# SCH1_MCU.net
KiCad netlist of a schematic drawn in Altium Designer
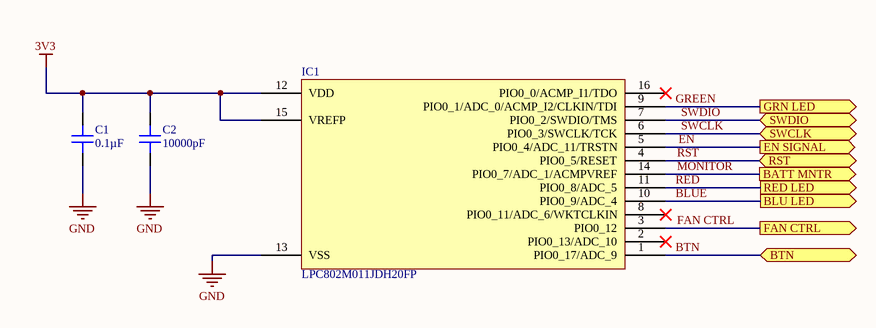
[diagram p0: SCH1_MCU.SchDoc]

(export (version "E")
  (design (tool "Eeschema 10.0.6"))
  (components
    (comp (ref "C1")
      (value "0.1µF")
      (footprint "CAP 0402_1005")
      (description "CAP CER 0.1UF 25V X5R 0402")
      (fields (field (name "PART NUMBER") "CC0402KRX5R8BB104") (field (name "MANUFACTURER") "Yageo"))
      (libsource (lib "Celestial Altium Library - altium_library") (part "Capacitor"))
    )
    (comp (ref "C2")
      (value "10000pF")
      (footprint "CAP 0402_1005")
      (description "CAP CER 10000PF 25V X5R 0402")
      (fields
        (field (name "PART NUMBER") "CGA2B2X5R1E103M050BA")
        (field (name "MANUFACTURER") "TDK Corporation")
      )
      (libsource (lib "Celestial Altium Library - altium_library") (part "Capacitor"))
    )
    (comp (ref "IC1")
      (value "LPC802M011JDH20FP")
      (footprint "NXP TSSOP-16")
      (description "Integrated CIrcuit")
      (libsource (lib "SCH - ARM CORTEX - NXP LPC80X 16PIN") (part "NXP LPC802 16PIN"))
    )
  )
  (nets
    (net (code "1") (name "/BLUE") (class "Default")
      (node (ref "IC1") (pin "10") (pinfunction "PIO0_9/ADC_4_10") (pintype "passive"))
    )
    (net (code "2") (name "/BTN") (class "Default")
      (node (ref "IC1") (pin "1") (pinfunction "PIO0_17/ADC_9_1") (pintype "passive"))
    )
    (net (code "3") (name "/EN") (class "Default")
      (node (ref "IC1") (pin "5") (pinfunction "PIO0_4/ADC_11/TRSTN_5") (pintype "passive"))
    )
    (net (code "4") (name "/FAN CTRL") (class "Default")
      (node (ref "IC1") (pin "3") (pinfunction "PIO0_12_3") (pintype "passive"))
    )
    (net (code "5") (name "/GREEN") (class "Default")
      (node (ref "IC1") (pin "9") (pinfunction "PIO0_1/ADC_0/ACMP_I2/CLKIN/TDI_9") (pintype "passive"))
    )
    (net (code "6") (name "/MONITOR") (class "Default")
      (node (ref "IC1") (pin "14") (pinfunction "PIO0_7/ADC_1/ACMPVREF_14") (pintype "passive"))
    )
    (net (code "7") (name "/RED") (class "Default")
      (node (ref "IC1") (pin "11") (pinfunction "PIO0_8/ADC_5_11") (pintype "passive"))
    )
    (net (code "8") (name "/RST") (class "Default")
      (node (ref "IC1") (pin "4") (pinfunction "PIO0_5/RESET_4") (pintype "passive"))
    )
    (net (code "9") (name "/SWCLK") (class "Default")
      (node (ref "IC1") (pin "6") (pinfunction "PIO0_3/SWCLK/TCK_6") (pintype "passive"))
    )
    (net (code "10") (name "/SWDIO") (class "Default")
      (node (ref "IC1") (pin "7") (pinfunction "PIO0_2/SWDIO/TMS_7") (pintype "passive"))
    )
    (net (code "11") (name "3V3") (class "Default")
      (node (ref "C1") (pin "2") (pinfunction "2_2") (pintype "passive"))
      (node (ref "C2") (pin "2") (pinfunction "2_2") (pintype "passive"))
      (node (ref "IC1") (pin "12") (pinfunction "VDD_12") (pintype "passive"))
      (node (ref "IC1") (pin "15") (pinfunction "VREFP_15") (pintype "passive"))
    )
    (net (code "12") (name "GND") (class "Default")
      (node (ref "C1") (pin "1") (pinfunction "1_1") (pintype "passive"))
      (node (ref "C2") (pin "1") (pinfunction "1_1") (pintype "passive"))
      (node (ref "IC1") (pin "13") (pinfunction "VSS_13") (pintype "passive"))
    )
    (net (code "13") (name "unconnected-(IC1-PIO0_0{slash}ACMP_I1{slash}TDO-Pad16)") (class "Default")
      (node (ref "IC1") (pin "16") (pinfunction "PIO0_0/ACMP_I1/TDO_16") (pintype "passive+no_connect"))
    )
    (net (code "14") (name "unconnected-(IC1-PIO0_11{slash}ADC_6{slash}WKTCLKIN-Pad8)") (class "Default")
      (node (ref "IC1") (pin "8") (pinfunction "PIO0_11/ADC_6/WKTCLKIN_8") (pintype "passive+no_connect"))
    )
    (net (code "15") (name "unconnected-(IC1-PIO0_13{slash}ADC_10-Pad2)") (class "Default")
      (node (ref "IC1") (pin "2") (pinfunction "PIO0_13/ADC_10_2") (pintype "passive+no_connect"))
    )
  )
)
